# IMU_Schematics.net
KiCad netlist of a schematic drawn in Altium Designer
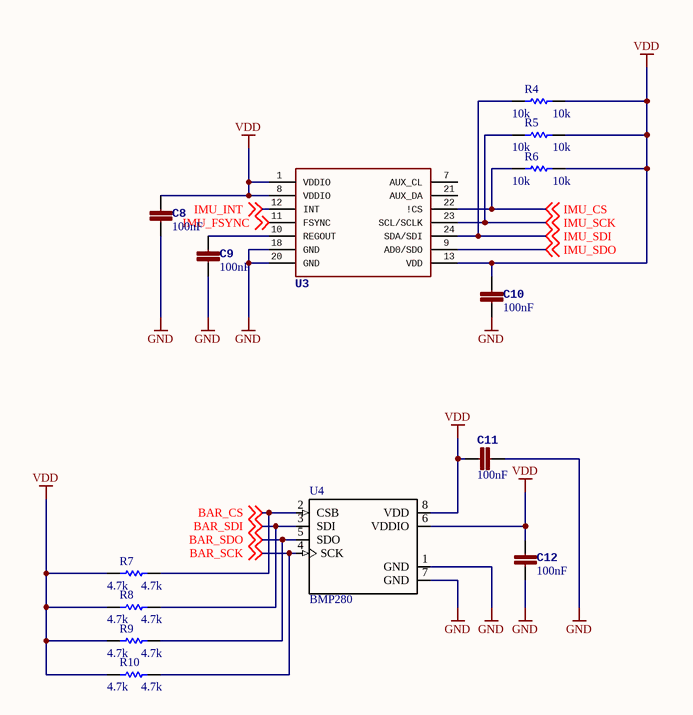
[diagram p0: IMU_Schematics.SchDoc]

(export (version "E")
  (design (tool "Eeschema 10.0.6"))
  (components
    (comp (ref "C8")
      (value "100nF")
      (footprint "_0603")
      (fields (field (name "Comment") "Cap"))
      (libsource (lib "") (part "Cap_1_1"))
    )
    (comp (ref "C9")
      (value "100nF")
      (footprint "_0603")
      (fields (field (name "Comment") "Cap"))
      (libsource (lib "") (part "Cap_1_1"))
    )
    (comp (ref "C10")
      (value "100nF")
      (footprint "_0603")
      (fields (field (name "Comment") "Cap"))
      (libsource (lib "") (part "Cap_1_1"))
    )
    (comp (ref "C11")
      (value "100nF")
      (footprint "_0603")
      (fields (field (name "Comment") "Cap"))
      (libsource (lib "Passives_Integrated_Library") (part "Cap_1"))
    )
    (comp (ref "C12")
      (value "100nF")
      (footprint "_0603")
      (fields (field (name "Comment") "Cap"))
      (libsource (lib "") (part "Cap_1_2"))
    )
    (comp (ref "R4")
      (value "10k")
      (footprint "RES0603")
      (description "TOTAL SMD RESISTOR PACK")
      (fields (field (name "ALTIUM_VALUE") "10k") (field (name "DESIGNER") "Abbas Basereh"))
      (libsource (lib "Passives_Integrated_Library") (part "RES SMD PACKAGE"))
    )
    (comp (ref "R5")
      (value "10k")
      (footprint "RES0603")
      (description "TOTAL SMD RESISTOR PACK")
      (fields (field (name "ALTIUM_VALUE") "10k") (field (name "DESIGNER") "Abbas Basereh"))
      (libsource (lib "Passives_Integrated_Library") (part "RES SMD PACKAGE"))
    )
    (comp (ref "R6")
      (value "10k")
      (footprint "RES0603")
      (description "TOTAL SMD RESISTOR PACK")
      (fields (field (name "ALTIUM_VALUE") "10k") (field (name "DESIGNER") "Abbas Basereh"))
      (libsource (lib "Passives_Integrated_Library") (part "RES SMD PACKAGE"))
    )
    (comp (ref "R7")
      (value "4.7k")
      (footprint "RES0603")
      (description "TOTAL SMD RESISTOR PACK")
      (fields (field (name "ALTIUM_VALUE") "4.7k") (field (name "DESIGNER") "Abbas Basereh"))
      (libsource (lib "Passives_Integrated_Library") (part "RES SMD PACKAGE"))
    )
    (comp (ref "R8")
      (value "4.7k")
      (footprint "RES0603")
      (description "TOTAL SMD RESISTOR PACK")
      (fields (field (name "ALTIUM_VALUE") "4.7k") (field (name "DESIGNER") "Abbas Basereh"))
      (libsource (lib "Passives_Integrated_Library") (part "RES SMD PACKAGE"))
    )
    (comp (ref "R9")
      (value "4.7k")
      (footprint "RES0603")
      (description "TOTAL SMD RESISTOR PACK")
      (fields (field (name "ALTIUM_VALUE") "4.7k") (field (name "DESIGNER") "Abbas Basereh"))
      (libsource (lib "Passives_Integrated_Library") (part "RES SMD PACKAGE"))
    )
    (comp (ref "R10")
      (value "4.7k")
      (footprint "RES0603")
      (description "TOTAL SMD RESISTOR PACK")
      (fields (field (name "ALTIUM_VALUE") "4.7k") (field (name "DESIGNER") "Abbas Basereh"))
      (libsource (lib "Passives_Integrated_Library") (part "RES SMD PACKAGE"))
    )
    (comp (ref "U3")
      (value "MPU-9250")
      (footprint "_QFN-24-EP")
      (libsource (lib "Sensors_Integrated_Library") (part "MPU-9250"))
    )
    (comp (ref "U4")
      (value "BMP280")
      (footprint "*XDCR_BMP280")
      (description "BMP280 Absolute Barometric Pressure Sensor for Battery Powered Devices 2 x 2.5mm")
      (fields (field (name "MF") "Bosch"))
      (libsource (lib "BMP280") (part "BMP280"))
    )
  )
  (nets
    (net (code "1") (name "BAR_CS") (class "Default")
      (node (ref "R7") (pin "2") (pinfunction "2_2") (pintype "passive"))
      (node (ref "U4") (pin "2") (pinfunction "CSB_2") (pintype "input"))
    )
    (net (code "2") (name "BAR_SCK") (class "Default")
      (node (ref "R10") (pin "2") (pinfunction "2_2") (pintype "passive"))
      (node (ref "U4") (pin "4") (pinfunction "SCK_4") (pintype "input"))
    )
    (net (code "3") (name "BAR_SDI") (class "Default")
      (node (ref "R8") (pin "2") (pinfunction "2_2") (pintype "passive"))
      (node (ref "U4") (pin "3") (pinfunction "SDI_3") (pintype "bidirectional"))
    )
    (net (code "4") (name "BAR_SDO") (class "Default")
      (node (ref "R9") (pin "2") (pinfunction "2_2") (pintype "passive"))
      (node (ref "U4") (pin "5") (pinfunction "SDO_5") (pintype "bidirectional"))
    )
    (net (code "5") (name "GND") (class "Default")
      (node (ref "C10") (pin "1") (pinfunction "1_1") (pintype "passive"))
      (node (ref "C11") (pin "2") (pinfunction "2_2") (pintype "passive"))
      (node (ref "C12") (pin "2") (pinfunction "2_2") (pintype "passive"))
      (node (ref "C8") (pin "1") (pinfunction "1_1") (pintype "passive"))
      (node (ref "C9") (pin "1") (pinfunction "1_1") (pintype "passive"))
      (node (ref "U3") (pin "18") (pinfunction "GND_18") (pintype "passive"))
      (node (ref "U3") (pin "20") (pinfunction "GND_20") (pintype "passive"))
      (node (ref "U4") (pin "1") (pinfunction "GND_1") (pintype "power_in"))
      (node (ref "U4") (pin "7") (pinfunction "GND_7") (pintype "power_in"))
    )
    (net (code "6") (name "IMU_CS") (class "Default")
      (node (ref "R6") (pin "1") (pinfunction "1_1") (pintype "passive"))
      (node (ref "U3") (pin "22") (pinfunction "!CS_22") (pintype "passive"))
    )
    (net (code "7") (name "IMU_FSYNC") (class "Default")
      (node (ref "U3") (pin "11") (pinfunction "FSYNC_11") (pintype "passive"))
    )
    (net (code "8") (name "IMU_INT") (class "Default")
      (node (ref "U3") (pin "12") (pinfunction "INT_12") (pintype "passive"))
    )
    (net (code "9") (name "IMU_SCK") (class "Default")
      (node (ref "R5") (pin "1") (pinfunction "1_1") (pintype "passive"))
      (node (ref "U3") (pin "23") (pinfunction "SCL/SCLK_23") (pintype "passive"))
    )
    (net (code "10") (name "IMU_SDI") (class "Default")
      (node (ref "R4") (pin "1") (pinfunction "1_1") (pintype "passive"))
      (node (ref "U3") (pin "24") (pinfunction "SDA/SDI_24") (pintype "passive"))
    )
    (net (code "11") (name "IMU_SDO") (class "Default")
      (node (ref "U3") (pin "9") (pinfunction "AD0/SDO_9") (pintype "passive"))
    )
    (net (code "12") (name "Net-(U3-REGOUT)") (class "Default")
      (node (ref "C9") (pin "2") (pinfunction "2_2") (pintype "passive"))
      (node (ref "U3") (pin "10") (pinfunction "REGOUT_10") (pintype "passive"))
    )
    (net (code "13") (name "VDD") (class "Default")
      (node (ref "C10") (pin "2") (pinfunction "2_2") (pintype "passive"))
      (node (ref "C11") (pin "1") (pinfunction "1_1") (pintype "passive"))
      (node (ref "C12") (pin "1") (pinfunction "1_1") (pintype "passive"))
      (node (ref "C8") (pin "2") (pinfunction "2_2") (pintype "passive"))
      (node (ref "R10") (pin "1") (pinfunction "1_1") (pintype "passive"))
      (node (ref "R4") (pin "2") (pinfunction "2_2") (pintype "passive"))
      (node (ref "R5") (pin "2") (pinfunction "2_2") (pintype "passive"))
      (node (ref "R6") (pin "2") (pinfunction "2_2") (pintype "passive"))
      (node (ref "R7") (pin "1") (pinfunction "1_1") (pintype "passive"))
      (node (ref "R8") (pin "1") (pinfunction "1_1") (pintype "passive"))
      (node (ref "R9") (pin "1") (pinfunction "1_1") (pintype "passive"))
      (node (ref "U3") (pin "1") (pinfunction "VDDIO_1") (pintype "passive"))
      (node (ref "U3") (pin "13") (pinfunction "VDD_13") (pintype "passive"))
      (node (ref "U3") (pin "8") (pinfunction "VDDIO_8") (pintype "passive"))
      (node (ref "U4") (pin "6") (pinfunction "VDDIO_6") (pintype "power_in"))
      (node (ref "U4") (pin "8") (pinfunction "VDD_8") (pintype "power_in"))
    )
    (net (code "14") (name "unconnected-(U3-AUX_CL-Pad7)") (class "Default")
      (node (ref "U3") (pin "7") (pinfunction "AUX_CL_7") (pintype "passive"))
    )
    (net (code "15") (name "unconnected-(U3-AUX_DA-Pad21)") (class "Default")
      (node (ref "U3") (pin "21") (pinfunction "AUX_DA_21") (pintype "passive"))
    )
  )
)
